# Fuentes.net
KiCad netlist of a schematic drawn in Altium Designer
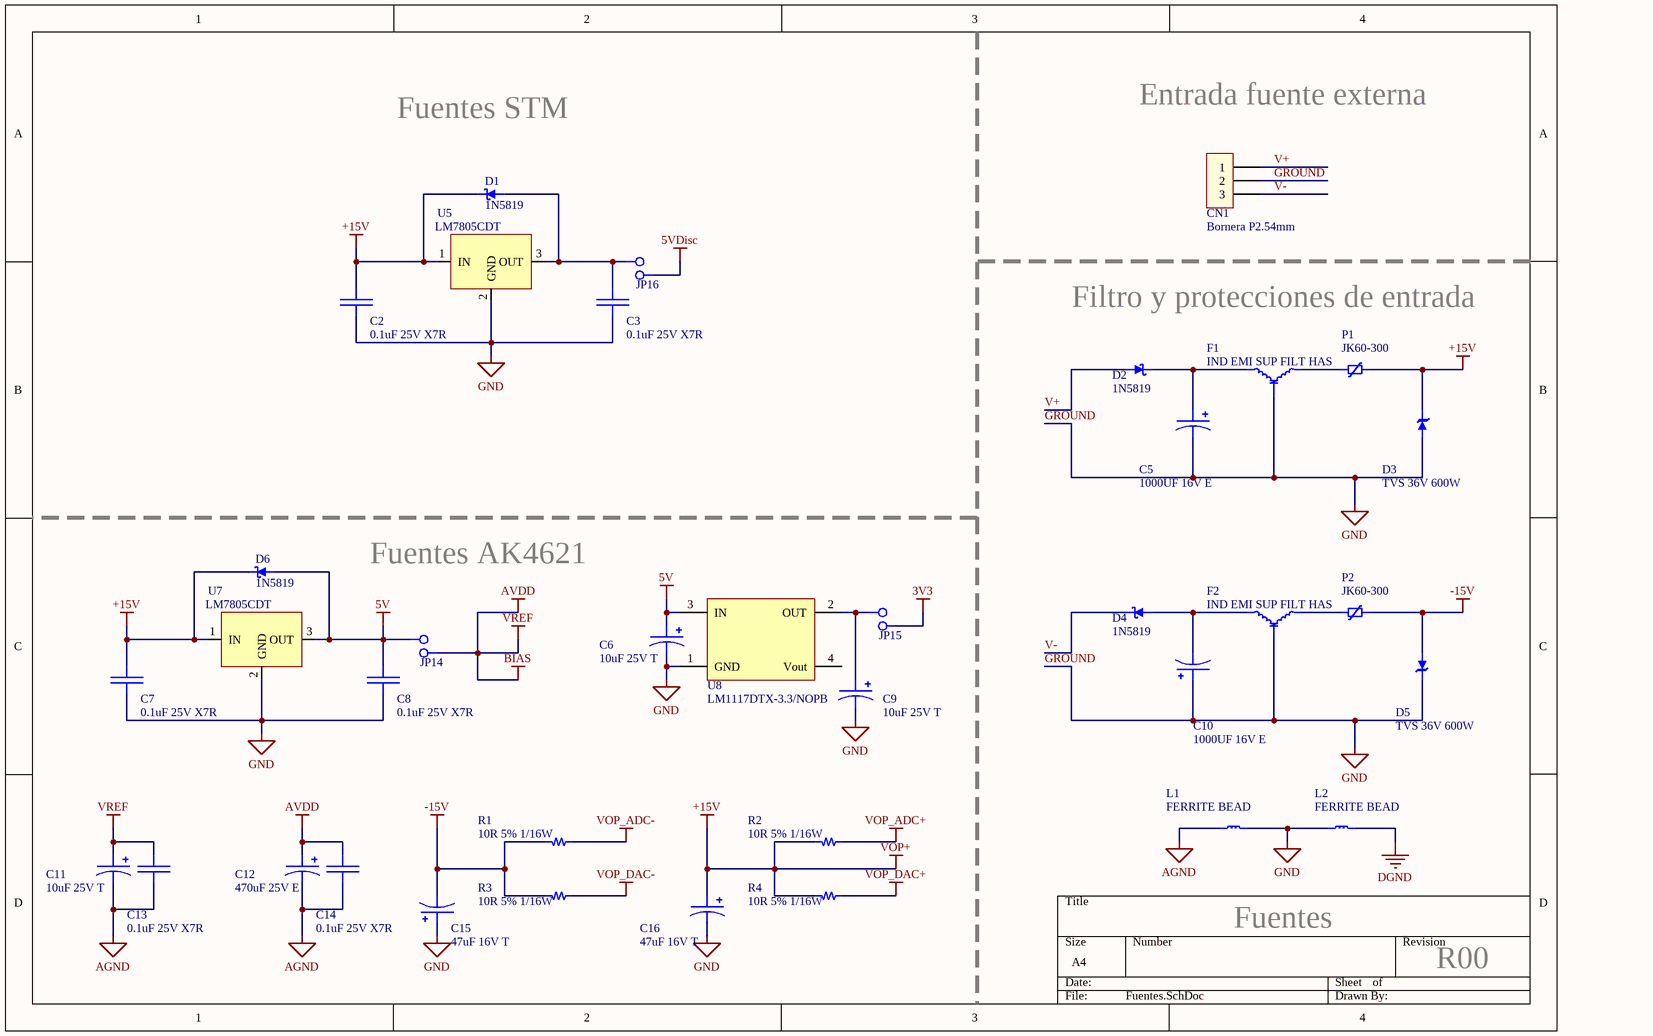
[diagram p0: Fuentes.SchDoc]

(export (version "E")
  (design (tool "Eeschema 10.0.6"))
  (components
    (comp (ref "C2")
      (value "0.1uF 25V X7R")
      (footprint "C_0805")
      (description "Capacitor de placas paralelas")
      (libsource (lib "Radios_Comunitarias") (part "Capacitor"))
    )
    (comp (ref "C3")
      (value "0.1uF 25V X7R")
      (footprint "C_0805")
      (description "Capacitor de placas paralelas")
      (libsource (lib "Radios_Comunitarias") (part "Capacitor"))
    )
    (comp (ref "C5")
      (value "1000UF 16V E")
      (footprint "Capael_10x16 RAD")
      (description "Capacitor polarizado")
      (libsource (lib "Radios_Comunitarias") (part "CapaPol"))
    )
    (comp (ref "C6")
      (value "10uF 25V T")
      (footprint "TANT")
      (description "Capacitor polarizado")
      (libsource (lib "Radios_Comunitarias") (part "CapaPol"))
    )
    (comp (ref "C7")
      (value "0.1uF 25V X7R")
      (footprint "C_0805")
      (description "Capacitor de placas paralelas")
      (libsource (lib "Radios_Comunitarias") (part "Capacitor"))
    )
    (comp (ref "C8")
      (value "0.1uF 25V X7R")
      (footprint "C_0805")
      (description "Capacitor de placas paralelas")
      (libsource (lib "Radios_Comunitarias") (part "Capacitor"))
    )
    (comp (ref "C9")
      (value "10uF 25V T")
      (footprint "TANT")
      (description "Capacitor polarizado")
      (libsource (lib "Radios_Comunitarias") (part "CapaPol"))
    )
    (comp (ref "C10")
      (value "1000UF 16V E")
      (footprint "Capael_10x16 RAD")
      (description "Capacitor polarizado")
      (libsource (lib "Radios_Comunitarias") (part "CapaPol"))
    )
    (comp (ref "C11")
      (value "10uF 25V T")
      (footprint "TANT")
      (description "Capacitor polarizado")
      (libsource (lib "Radios_Comunitarias") (part "CapaPol"))
    )
    (comp (ref "C12")
      (value "470uF 25V E")
      (footprint "Capael_8x12 RAD")
      (description "Capacitor polarizado")
      (libsource (lib "Radios_Comunitarias") (part "CapaPol"))
    )
    (comp (ref "C13")
      (value "0.1uF 25V X7R")
      (footprint "C_0805")
      (description "Capacitor de placas paralelas")
      (libsource (lib "Radios_Comunitarias") (part "Capacitor"))
    )
    (comp (ref "C14")
      (value "0.1uF 25V X7R")
      (footprint "C_0805")
      (description "Capacitor de placas paralelas")
      (libsource (lib "Radios_Comunitarias") (part "Capacitor"))
    )
    (comp (ref "C15")
      (value "47uF 16V T")
      (footprint "TANT")
      (description "Capacitor polarizado")
      (libsource (lib "Radios_Comunitarias") (part "CapaPol"))
    )
    (comp (ref "C16")
      (value "47uF 16V T")
      (footprint "TANT")
      (description "Capacitor polarizado")
      (libsource (lib "Radios_Comunitarias") (part "CapaPol"))
    )
    (comp (ref "CN1")
      (value "Bornera P2.54mm")
      (footprint "Conn_3_1")
      (description "Conector de 3 pines en hilera")
      (libsource (lib "Radios_Comunitarias") (part "Conn_3_1"))
    )
    (comp (ref "D1")
      (value "1N5819")
      (footprint "59-04")
      (description "Diodo Schottky")
      (libsource (lib "Radios_Comunitarias") (part "Schottky"))
    )
    (comp (ref "D2")
      (value "1N5819")
      (footprint "59-04")
      (description "Diodo Schottky")
      (libsource (lib "Radios_Comunitarias") (part "Schottky"))
    )
    (comp (ref "D3")
      (value "TVS 36V 600W")
      (footprint "59-04")
      (description "Diodo TVS")
      (libsource (lib "Radios_Comunitarias") (part "TVS"))
    )
    (comp (ref "D4")
      (value "1N5819")
      (footprint "59-04")
      (description "Diodo Schottky")
      (libsource (lib "Radios_Comunitarias") (part "Schottky"))
    )
    (comp (ref "D5")
      (value "TVS 36V 600W")
      (footprint "59-04")
      (description "Diodo TVS")
      (libsource (lib "Radios_Comunitarias") (part "TVS"))
    )
    (comp (ref "D6")
      (value "1N5819")
      (footprint "59-04")
      (description "Diodo Schottky")
      (libsource (lib "Radios_Comunitarias") (part "Schottky"))
    )
    (comp (ref "F1")
      (value "IND EMI SUP FILT HAS")
      (footprint "EMIFIL_DSS6_S")
      (description "Filtro EMI 3 terminales")
      (libsource (lib "Radios_Comunitarias") (part "EMI_3T"))
    )
    (comp (ref "F2")
      (value "IND EMI SUP FILT HAS")
      (footprint "EMIFIL_DSS6_S")
      (description "Filtro EMI 3 terminales")
      (libsource (lib "Radios_Comunitarias") (part "EMI_3T"))
    )
    (comp (ref "JP14")
      (value "Jumper 2x1")
      (footprint "Conn_2_1")
      (libsource (lib "Radios_Comunitarias") (part "Jumper 2x1"))
    )
    (comp (ref "JP15")
      (value "Jumper 2x1")
      (footprint "Conn_2_1")
      (libsource (lib "Radios_Comunitarias") (part "Jumper 2x1"))
    )
    (comp (ref "JP16")
      (value "Jumper 2x1")
      (footprint "Conn_2_1")
      (libsource (lib "Radios_Comunitarias") (part "Jumper 2x1"))
    )
    (comp (ref "L1")
      (value "FERRITE BEAD")
      (footprint "EC22/KC204")
      (description "Inductor")
      (libsource (lib "Radios_Comunitarias") (part "Inductor"))
    )
    (comp (ref "L2")
      (value "FERRITE BEAD")
      (footprint "EC22/KC204")
      (description "Inductor")
      (libsource (lib "Radios_Comunitarias") (part "Inductor"))
    )
    (comp (ref "P1")
      (value "JK60-300")
      (footprint "JK60-300")
      (description "Poly")
      (libsource (lib "Radios_Comunitarias") (part "Poly"))
    )
    (comp (ref "P2")
      (value "JK60-300")
      (footprint "JK60-300")
      (description "Poly")
      (libsource (lib "Radios_Comunitarias") (part "Poly"))
    )
    (comp (ref "R1")
      (value "10R 5% 1/16W")
      (footprint "R_0805")
      (description "Resistencia")
      (libsource (lib "Radios_Comunitarias") (part "Resistor"))
    )
    (comp (ref "R2")
      (value "10R 5% 1/16W")
      (footprint "R_0805")
      (description "Resistencia")
      (libsource (lib "Radios_Comunitarias") (part "Resistor"))
    )
    (comp (ref "R3")
      (value "10R 5% 1/16W")
      (footprint "R_0805")
      (description "Resistencia")
      (libsource (lib "Radios_Comunitarias") (part "Resistor"))
    )
    (comp (ref "R4")
      (value "10R 5% 1/16W")
      (footprint "R_0805")
      (description "Resistencia")
      (libsource (lib "Radios_Comunitarias") (part "Resistor"))
    )
    (comp (ref "U5")
      (value "LM7805CDT")
      (footprint "TO-220-3")
      (description "Regulador lineal 5V")
      (libsource (lib "Radios_Comunitarias") (part "LM7805"))
    )
    (comp (ref "U7")
      (value "LM7805CDT")
      (footprint "TO-220-3")
      (description "Regulador lineal 5V")
      (libsource (lib "Radios_Comunitarias") (part "LM7805"))
    )
    (comp (ref "U8")
      (value "LM1117DTX-3.3/NOPB")
      (footprint "DPAK")
      (description "Regulador Switching")
      (libsource (lib "Radios_Comunitarias") (part "LM1117"))
    )
  )
  (nets
    (net (code "1") (name "+15V") (class "Default")
      (node (ref "C16") (pin "1") (pinfunction "1_1") (pintype "passive"))
      (node (ref "C2") (pin "1") (pinfunction "1_1") (pintype "passive"))
      (node (ref "C7") (pin "1") (pinfunction "1_1") (pintype "passive"))
      (node (ref "D1") (pin "2") (pinfunction "2_2") (pintype "passive"))
      (node (ref "D3") (pin "2") (pinfunction "2_2") (pintype "passive"))
      (node (ref "D6") (pin "2") (pinfunction "2_2") (pintype "passive"))
      (node (ref "P1") (pin "2") (pinfunction "2_2") (pintype "passive"))
      (node (ref "R2") (pin "2") (pinfunction "2_2") (pintype "passive"))
      (node (ref "R4") (pin "2") (pinfunction "2_2") (pintype "passive"))
      (node (ref "U5") (pin "1") (pinfunction "IN_1") (pintype "passive"))
      (node (ref "U7") (pin "1") (pinfunction "IN_1") (pintype "passive"))
    )
    (net (code "2") (name "-15V") (class "Default")
      (node (ref "C15") (pin "2") (pinfunction "2_2") (pintype "passive"))
      (node (ref "D5") (pin "1") (pinfunction "¦_1") (pintype "passive"))
      (node (ref "P2") (pin "2") (pinfunction "2_2") (pintype "passive"))
      (node (ref "R1") (pin "2") (pinfunction "2_2") (pintype "passive"))
      (node (ref "R3") (pin "2") (pinfunction "2_2") (pintype "passive"))
    )
    (net (code "3") (name "/V+") (class "Default")
      (node (ref "CN1") (pin "1") (pinfunction "1_1") (pintype "passive"))
      (node (ref "D2") (pin "1") (pinfunction "¦_1") (pintype "passive"))
    )
    (net (code "4") (name "/V-") (class "Default")
      (node (ref "CN1") (pin "3") (pinfunction "3_3") (pintype "passive"))
      (node (ref "D4") (pin "2") (pinfunction "2_2") (pintype "passive"))
    )
    (net (code "5") (name "3V3") (class "Default")
      (node (ref "JP15") (pin "2") (pinfunction "2_2") (pintype "passive"))
    )
    (net (code "6") (name "5V") (class "Default")
      (node (ref "C6") (pin "1") (pinfunction "1_1") (pintype "passive"))
      (node (ref "C8") (pin "1") (pinfunction "1_1") (pintype "passive"))
      (node (ref "D6") (pin "1") (pinfunction "¦_1") (pintype "passive"))
      (node (ref "JP14") (pin "1") (pinfunction "1_1") (pintype "passive"))
      (node (ref "U7") (pin "3") (pinfunction "OUT_3") (pintype "passive"))
      (node (ref "U8") (pin "3") (pinfunction "IN_3") (pintype "passive"))
    )
    (net (code "7") (name "5VDisc") (class "Default")
      (node (ref "JP16") (pin "2") (pinfunction "2_2") (pintype "passive"))
    )
    (net (code "8") (name "AGND") (class "Default")
      (node (ref "C11") (pin "2") (pinfunction "2_2") (pintype "passive"))
      (node (ref "C12") (pin "2") (pinfunction "2_2") (pintype "passive"))
      (node (ref "C13") (pin "2") (pinfunction "2_2") (pintype "passive"))
      (node (ref "C14") (pin "2") (pinfunction "2_2") (pintype "passive"))
      (node (ref "L1") (pin "1") (pinfunction "1_1") (pintype "passive"))
    )
    (net (code "9") (name "AVDD") (class "Default")
      (node (ref "C11") (pin "1") (pinfunction "1_1") (pintype "passive"))
      (node (ref "C12") (pin "1") (pinfunction "1_1") (pintype "passive"))
      (node (ref "C13") (pin "1") (pinfunction "1_1") (pintype "passive"))
      (node (ref "C14") (pin "1") (pinfunction "1_1") (pintype "passive"))
      (node (ref "JP14") (pin "2") (pinfunction "2_2") (pintype "passive"))
    )
    (net (code "10") (name "DGND") (class "Default")
      (node (ref "L2") (pin "2") (pinfunction "2_2") (pintype "passive"))
    )
    (net (code "11") (name "GND") (class "Default")
      (node (ref "C10") (pin "1") (pinfunction "1_1") (pintype "passive"))
      (node (ref "C15") (pin "1") (pinfunction "1_1") (pintype "passive"))
      (node (ref "C16") (pin "2") (pinfunction "2_2") (pintype "passive"))
      (node (ref "C2") (pin "2") (pinfunction "2_2") (pintype "passive"))
      (node (ref "C3") (pin "2") (pinfunction "2_2") (pintype "passive"))
      (node (ref "C5") (pin "2") (pinfunction "2_2") (pintype "passive"))
      (node (ref "C6") (pin "2") (pinfunction "2_2") (pintype "passive"))
      (node (ref "C7") (pin "2") (pinfunction "2_2") (pintype "passive"))
      (node (ref "C8") (pin "2") (pinfunction "2_2") (pintype "passive"))
      (node (ref "C9") (pin "2") (pinfunction "2_2") (pintype "passive"))
      (node (ref "CN1") (pin "2") (pinfunction "2_2") (pintype "passive"))
      (node (ref "D3") (pin "1") (pinfunction "¦_1") (pintype "passive"))
      (node (ref "D5") (pin "2") (pinfunction "2_2") (pintype "passive"))
      (node (ref "F1") (pin "2") (pinfunction "2_2") (pintype "passive"))
      (node (ref "F2") (pin "2") (pinfunction "2_2") (pintype "passive"))
      (node (ref "L1") (pin "2") (pinfunction "2_2") (pintype "passive"))
      (node (ref "L2") (pin "1") (pinfunction "1_1") (pintype "passive"))
      (node (ref "U5") (pin "2") (pinfunction "GND_2") (pintype "passive"))
      (node (ref "U7") (pin "2") (pinfunction "GND_2") (pintype "passive"))
      (node (ref "U8") (pin "1") (pinfunction "GND_1") (pintype "passive"))
    )
    (net (code "12") (name "Net-(C5-Pad1)") (class "Default")
      (node (ref "C5") (pin "1") (pinfunction "1_1") (pintype "passive"))
      (node (ref "D2") (pin "2") (pinfunction "2_2") (pintype "passive"))
      (node (ref "F1") (pin "1") (pinfunction "1_1") (pintype "passive"))
    )
    (net (code "13") (name "Net-(D1-¦)") (class "Default")
      (node (ref "C3") (pin "1") (pinfunction "1_1") (pintype "passive"))
      (node (ref "D1") (pin "1") (pinfunction "¦_1") (pintype "passive"))
      (node (ref "JP16") (pin "1") (pinfunction "1_1") (pintype "passive"))
      (node (ref "U5") (pin "3") (pinfunction "OUT_3") (pintype "passive"))
    )
    (net (code "14") (name "Net-(D4-¦)") (class "Default")
      (node (ref "C10") (pin "2") (pinfunction "2_2") (pintype "passive"))
      (node (ref "D4") (pin "1") (pinfunction "¦_1") (pintype "passive"))
      (node (ref "F2") (pin "1") (pinfunction "1_1") (pintype "passive"))
    )
    (net (code "15") (name "Net-(F1-Pad3)") (class "Default")
      (node (ref "F1") (pin "3") (pinfunction "3_3") (pintype "passive"))
      (node (ref "P1") (pin "1") (pinfunction "1_1") (pintype "passive"))
    )
    (net (code "16") (name "Net-(F2-Pad3)") (class "Default")
      (node (ref "F2") (pin "3") (pinfunction "3_3") (pintype "passive"))
      (node (ref "P2") (pin "1") (pinfunction "1_1") (pintype "passive"))
    )
    (net (code "17") (name "Net-(U8-OUT)") (class "Default")
      (node (ref "C9") (pin "1") (pinfunction "1_1") (pintype "passive"))
      (node (ref "JP15") (pin "1") (pinfunction "1_1") (pintype "passive"))
      (node (ref "U8") (pin "2") (pinfunction "OUT_2") (pintype "passive"))
    )
    (net (code "18") (name "VOP_ADC+") (class "Default")
      (node (ref "R2") (pin "1") (pinfunction "1_1") (pintype "passive"))
    )
    (net (code "19") (name "VOP_ADC-") (class "Default")
      (node (ref "R1") (pin "1") (pinfunction "1_1") (pintype "passive"))
    )
    (net (code "20") (name "VOP_DAC+") (class "Default")
      (node (ref "R4") (pin "1") (pinfunction "1_1") (pintype "passive"))
    )
    (net (code "21") (name "VOP_DAC-") (class "Default")
      (node (ref "R3") (pin "1") (pinfunction "1_1") (pintype "passive"))
    )
    (net (code "22") (name "unconnected-(U8-Vout-Pad4)") (class "Default")
      (node (ref "U8") (pin "4") (pinfunction "Vout_4") (pintype "passive"))
    )
  )
)
